# powerSupply.net
KiCad netlist of a schematic drawn in EAGLE
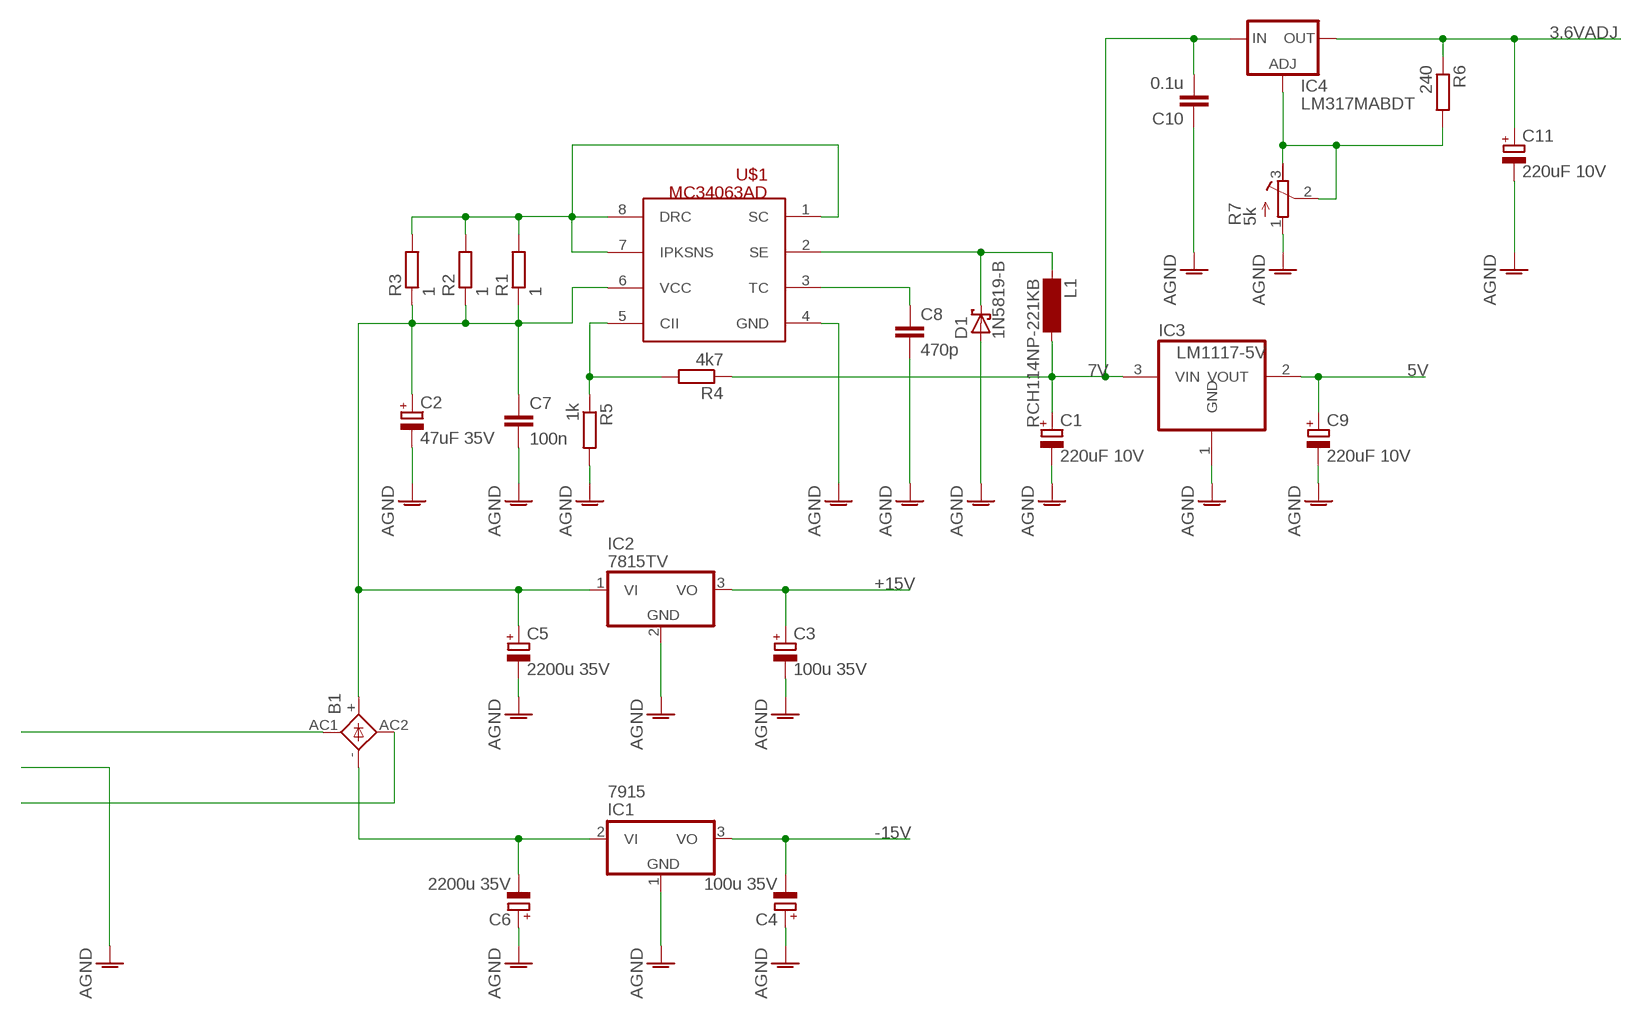
[diagram p0: schematic, sheet 1]

(export (version "E")
  (design (tool "Eeschema 10.0.6"))
  (components
    (comp (ref "B1")
      (value "2KBP")
      (footprint "eagle-import:2KBP")
      (libsource (lib "eagle-import") (part "2KBP"))
    )
    (comp (ref "C1")
      (value "220uF 10V")
      (footprint "eagle-import:UD-6,3X5,8_NICHICON")
      (libsource (lib "eagle-import") (part "CPOL-EUUD-6,3X8,8"))
    )
    (comp (ref "C2")
      (value "47uF 35V")
      (footprint "eagle-import:UD-6,3X7,7_NICHICON")
      (libsource (lib "eagle-import") (part "CPOL-EUUD-6,3X7,7"))
    )
    (comp (ref "C3")
      (value "100u 35V")
      (footprint "eagle-import:E3,5-8")
      (libsource (lib "eagle-import") (part "CPOL-EUE3.5-8"))
    )
    (comp (ref "C4")
      (value "100u 35V")
      (footprint "eagle-import:E3,5-8")
      (libsource (lib "eagle-import") (part "CPOL-EUE3.5-8"))
    )
    (comp (ref "C5")
      (value "2200u 35V")
      (footprint "eagle-import:E7,5-16")
      (libsource (lib "eagle-import") (part "CPOL-EUE7.5-16"))
    )
    (comp (ref "C6")
      (value "2200u 35V")
      (footprint "eagle-import:E7,5-16")
      (libsource (lib "eagle-import") (part "CPOL-EUE7.5-16"))
    )
    (comp (ref "C7")
      (value "100n")
      (footprint "eagle-import:C0805")
      (libsource (lib "eagle-import") (part "C-EUC0805"))
    )
    (comp (ref "C8")
      (value "470p")
      (footprint "eagle-import:C0805")
      (libsource (lib "eagle-import") (part "C-EUC0805"))
    )
    (comp (ref "C9")
      (value "220uF 10V")
      (footprint "eagle-import:UD-6,3X5,8_NICHICON")
      (libsource (lib "eagle-import") (part "CPOL-EUUD-6,3X8,8"))
    )
    (comp (ref "C10")
      (value "0.1u")
      (footprint "eagle-import:C0805")
      (libsource (lib "eagle-import") (part "C-EUC0805"))
    )
    (comp (ref "C11")
      (value "220uF 10V")
      (footprint "eagle-import:UD-6,3X5,8_NICHICON")
      (libsource (lib "eagle-import") (part "CPOL-EUUD-6,3X8,8"))
    )
    (comp (ref "D1")
      (value "1N5819-B")
      (footprint "eagle-import:DO41-7.6")
      (libsource (lib "eagle-import") (part "1N5819-B"))
    )
    (comp (ref "IC1")
      (value "7915")
      (footprint "eagle-import:TO220V")
      (libsource (lib "eagle-import") (part "79V15"))
    )
    (comp (ref "IC2")
      (value "7815TV")
      (footprint "eagle-import:TO220V")
      (libsource (lib "eagle-import") (part "78TV15"))
    )
    (comp (ref "IC3")
      (value "LM1117-5V")
      (footprint "eagle-import:SOT223")
      (fields (field (name "MPN") "REG1117"))
      (libsource (lib "eagle-import") (part "REG1117"))
    )
    (comp (ref "IC4")
      (value "LM317MABDT")
      (footprint "eagle-import:DPACK")
      (libsource (lib "eagle-import") (part "v-reg_LM317?MABDT"))
    )
    (comp (ref "L1")
      (value "RCH114NP-221KB")
      (footprint "eagle-import:BS11")
      (libsource (lib "eagle-import") (part "BS11"))
    )
    (comp (ref "R1")
      (value "1")
      (footprint "eagle-import:M1206")
      (libsource (lib "eagle-import") (part "R-EU_M1206"))
    )
    (comp (ref "R2")
      (value "1")
      (footprint "eagle-import:M1206")
      (libsource (lib "eagle-import") (part "R-EU_M1206"))
    )
    (comp (ref "R3")
      (value "1")
      (footprint "eagle-import:M1206")
      (libsource (lib "eagle-import") (part "R-EU_M1206"))
    )
    (comp (ref "R4")
      (value "4k7")
      (footprint "eagle-import:M1206")
      (libsource (lib "eagle-import") (part "R-EU_M1206"))
    )
    (comp (ref "R5")
      (value "1k")
      (footprint "eagle-import:M1206")
      (libsource (lib "eagle-import") (part "R-EU_M1206"))
    )
    (comp (ref "R6")
      (value "240")
      (footprint "eagle-import:M1206")
      (libsource (lib "eagle-import") (part "R-EU_M1206"))
    )
    (comp (ref "R7")
      (value "5k")
      (footprint "eagle-import:RTRIM3296W")
      (libsource (lib "eagle-import") (part "R-TRIMM3296W"))
    )
    (comp (ref "U$1")
      (value "MC34063AD")
      (footprint "eagle-import:SO-08")
      (libsource (lib "eagle-import") (part "MC34063AD"))
    )
  )
  (nets
    (net (code "1") (name "/+15V") (class "Default")
      (node (ref "C3") (pin "+") (pinfunction "+_+") (pintype "passive"))
      (node (ref "IC2") (pin "3") (pinfunction "VO_3") (pintype "passive"))
    )
    (net (code "2") (name "/-15V") (class "Default")
      (node (ref "C4") (pin "-") (pinfunction "-_-") (pintype "passive"))
      (node (ref "IC1") (pin "3") (pinfunction "VO_3") (pintype "passive"))
    )
    (net (code "3") (name "/3.6VADJ") (class "Default")
      (node (ref "C11") (pin "+") (pinfunction "+_+") (pintype "passive"))
      (node (ref "IC4") (pin "4") (pinfunction "OUT_4") (pintype "passive"))
      (node (ref "R6") (pin "1") (pinfunction "1_1") (pintype "passive"))
    )
    (net (code "4") (name "/5V") (class "Default")
      (node (ref "C9") (pin "+") (pinfunction "+_+") (pintype "passive"))
      (node (ref "IC3") (pin "2") (pinfunction "VOUT_2") (pintype "output"))
    )
    (net (code "5") (name "/7V") (class "Default")
      (node (ref "C1") (pin "+") (pinfunction "+_+") (pintype "passive"))
      (node (ref "C10") (pin "2") (pinfunction "2_2") (pintype "passive"))
      (node (ref "IC3") (pin "3") (pinfunction "VIN_3") (pintype "input"))
      (node (ref "IC4") (pin "3") (pinfunction "IN_3") (pintype "input"))
      (node (ref "L1") (pin "2") (pinfunction "2_2") (pintype "passive"))
      (node (ref "R4") (pin "1") (pinfunction "1_1") (pintype "passive"))
    )
    (net (code "6") (name "AGND") (class "Default")
      (node (ref "C1") (pin "-") (pinfunction "-_-") (pintype "passive"))
      (node (ref "C10") (pin "1") (pinfunction "1_1") (pintype "passive"))
      (node (ref "C11") (pin "-") (pinfunction "-_-") (pintype "passive"))
      (node (ref "C2") (pin "-") (pinfunction "-_-") (pintype "passive"))
      (node (ref "C3") (pin "-") (pinfunction "-_-") (pintype "passive"))
      (node (ref "C4") (pin "+") (pinfunction "+_+") (pintype "passive"))
      (node (ref "C5") (pin "-") (pinfunction "-_-") (pintype "passive"))
      (node (ref "C6") (pin "+") (pinfunction "+_+") (pintype "passive"))
      (node (ref "C7") (pin "2") (pinfunction "2_2") (pintype "passive"))
      (node (ref "C8") (pin "2") (pinfunction "2_2") (pintype "passive"))
      (node (ref "C9") (pin "-") (pinfunction "-_-") (pintype "passive"))
      (node (ref "D1") (pin "A") (pinfunction "A_A") (pintype "passive"))
      (node (ref "IC1") (pin "1") (pinfunction "GND_1") (pintype "passive"))
      (node (ref "IC2") (pin "2") (pinfunction "GND_2") (pintype "passive"))
      (node (ref "IC3") (pin "1") (pinfunction "GND_1") (pintype "power_in"))
      (node (ref "R5") (pin "2") (pinfunction "2_2") (pintype "passive"))
      (node (ref "R7") (pin "1") (pinfunction "A_1") (pintype "passive"))
      (node (ref "U$1") (pin "4") (pinfunction "GND_4") (pintype "power_in"))
    )
    (net (code "7") (name "Net-(IC1-VI)") (class "Default")
      (node (ref "B1") (pin "-") (pinfunction "-_-") (pintype "passive"))
      (node (ref "C6") (pin "-") (pinfunction "-_-") (pintype "passive"))
      (node (ref "IC1") (pin "2") (pinfunction "VI_2") (pintype "input"))
    )
    (net (code "8") (name "Net-(IC2-VI)") (class "Default")
      (node (ref "B1") (pin "+") (pinfunction "+_+") (pintype "passive"))
      (node (ref "C2") (pin "+") (pinfunction "+_+") (pintype "passive"))
      (node (ref "C5") (pin "+") (pinfunction "+_+") (pintype "passive"))
      (node (ref "C7") (pin "1") (pinfunction "1_1") (pintype "passive"))
      (node (ref "IC2") (pin "1") (pinfunction "VI_1") (pintype "input"))
      (node (ref "R1") (pin "1") (pinfunction "1_1") (pintype "passive"))
      (node (ref "R2") (pin "1") (pinfunction "1_1") (pintype "passive"))
      (node (ref "R3") (pin "1") (pinfunction "1_1") (pintype "passive"))
      (node (ref "U$1") (pin "6") (pinfunction "VCC_6") (pintype "power_in"))
    )
    (net (code "9") (name "Net-(IC4-ADJ)") (class "Default")
      (node (ref "IC4") (pin "1") (pinfunction "ADJ_1") (pintype "input"))
      (node (ref "R6") (pin "2") (pinfunction "2_2") (pintype "passive"))
      (node (ref "R7") (pin "2") (pinfunction "S_2") (pintype "passive"))
      (node (ref "R7") (pin "3") (pinfunction "E_3") (pintype "passive"))
    )
    (net (code "10") (name "Net-(U$1-CII)") (class "Default")
      (node (ref "R4") (pin "2") (pinfunction "2_2") (pintype "passive"))
      (node (ref "R5") (pin "1") (pinfunction "1_1") (pintype "passive"))
      (node (ref "U$1") (pin "5") (pinfunction "CII_5") (pintype "power_in"))
    )
    (net (code "11") (name "Net-(U$1-DRC)") (class "Default")
      (node (ref "R1") (pin "2") (pinfunction "2_2") (pintype "passive"))
      (node (ref "R2") (pin "2") (pinfunction "2_2") (pintype "passive"))
      (node (ref "R3") (pin "2") (pinfunction "2_2") (pintype "passive"))
      (node (ref "U$1") (pin "1") (pinfunction "SC_1") (pintype "power_in"))
      (node (ref "U$1") (pin "7") (pinfunction "IPKSNS_7") (pintype "power_in"))
      (node (ref "U$1") (pin "8") (pinfunction "DRC_8") (pintype "power_in"))
    )
    (net (code "12") (name "Net-(U$1-SE)") (class "Default")
      (node (ref "D1") (pin "C") (pinfunction "C_C") (pintype "passive"))
      (node (ref "L1") (pin "1") (pinfunction "1_1") (pintype "passive"))
      (node (ref "U$1") (pin "2") (pinfunction "SE_2") (pintype "power_in"))
    )
    (net (code "13") (name "Net-(U$1-TC)") (class "Default")
      (node (ref "C8") (pin "1") (pinfunction "1_1") (pintype "passive"))
      (node (ref "U$1") (pin "3") (pinfunction "TC_3") (pintype "power_in"))
    )
    (net (code "14") (name "unconnected-(B1-PadAC1)") (class "Default")
      (node (ref "B1") (pin "AC1") (pinfunction "AC1_AC1") (pintype "passive"))
    )
    (net (code "15") (name "unconnected-(B1-PadAC2)") (class "Default")
      (node (ref "B1") (pin "AC2") (pinfunction "AC2_AC2") (pintype "passive"))
    )
  )
)
